# lab05.net
KiCad netlist of a schematic drawn in EAGLE
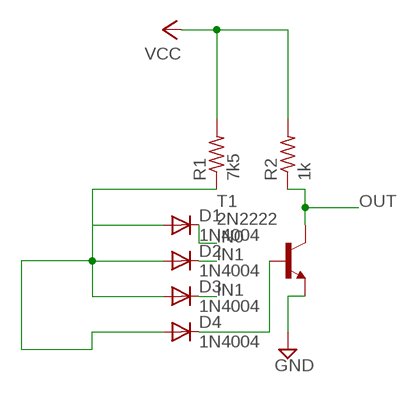
[diagram p0: schematic, sheet 1]

(export (version "E")
  (design (tool "Eeschema 10.0.6"))
  (components
    (comp (ref "D1")
      (value "1N4004")
      (footprint "eagle-import:DO41-10")
      (libsource (lib "eagle-import") (part "1N4004"))
    )
    (comp (ref "D2")
      (value "1N4004")
      (footprint "eagle-import:DO41-10")
      (libsource (lib "eagle-import") (part "1N4004"))
    )
    (comp (ref "D3")
      (value "1N4004")
      (footprint "eagle-import:DO41-10")
      (libsource (lib "eagle-import") (part "1N4004"))
    )
    (comp (ref "D4")
      (value "1N4004")
      (footprint "eagle-import:DO41-10")
      (libsource (lib "eagle-import") (part "1N4004"))
    )
    (comp (ref "R1")
      (value "7k5")
      (footprint "eagle-import:0204_5")
      (libsource (lib "eagle-import") (part "R-US_0204/5"))
    )
    (comp (ref "R2")
      (value "1k")
      (footprint "eagle-import:0204_5")
      (libsource (lib "eagle-import") (part "R-US_0204/5"))
    )
    (comp (ref "T1")
      (value "2N2222")
      (footprint "eagle-import:TO92-EBC-OVAL")
      (libsource (lib "eagle-import") (part "2N2222"))
    )
  )
  (nets
    (net (code "1") (name "/IN0") (class "Default")
      (node (ref "D1") (pin "C") (pinfunction "C_C") (pintype "passive"))
    )
    (net (code "2") (name "/IN1") (class "Default")
      (node (ref "D2") (pin "C") (pinfunction "C_C") (pintype "passive"))
    )
    (net (code "3") (name "/OUT") (class "Default")
      (node (ref "R2") (pin "1") (pinfunction "1_1") (pintype "passive"))
      (node (ref "T1") (pin "C") (pinfunction "C_C") (pintype "passive"))
    )
    (net (code "4") (name "GND") (class "Default")
      (node (ref "T1") (pin "E") (pinfunction "E_E") (pintype "passive"))
    )
    (net (code "5") (name "Net-(D1-PadA)") (class "Default")
      (node (ref "D1") (pin "A") (pinfunction "A_A") (pintype "passive"))
      (node (ref "D2") (pin "A") (pinfunction "A_A") (pintype "passive"))
      (node (ref "D3") (pin "A") (pinfunction "A_A") (pintype "passive"))
      (node (ref "D4") (pin "A") (pinfunction "A_A") (pintype "passive"))
      (node (ref "R1") (pin "1") (pinfunction "1_1") (pintype "passive"))
    )
    (net (code "6") (name "Net-(D4-PadC)") (class "Default")
      (node (ref "D4") (pin "C") (pinfunction "C_C") (pintype "passive"))
      (node (ref "T1") (pin "B") (pinfunction "B_B") (pintype "passive"))
    )
    (net (code "7") (name "VCC") (class "Default")
      (node (ref "R1") (pin "2") (pinfunction "2_2") (pintype "passive"))
      (node (ref "R2") (pin "2") (pinfunction "2_2") (pintype "passive"))
    )
    (net (code "8") (name "unconnected-(D3-PadC)") (class "Default")
      (node (ref "D3") (pin "C") (pinfunction "C_C") (pintype "passive"))
    )
  )
)
